# ESP32_Sheet.net
KiCad netlist of a schematic drawn in Altium Designer
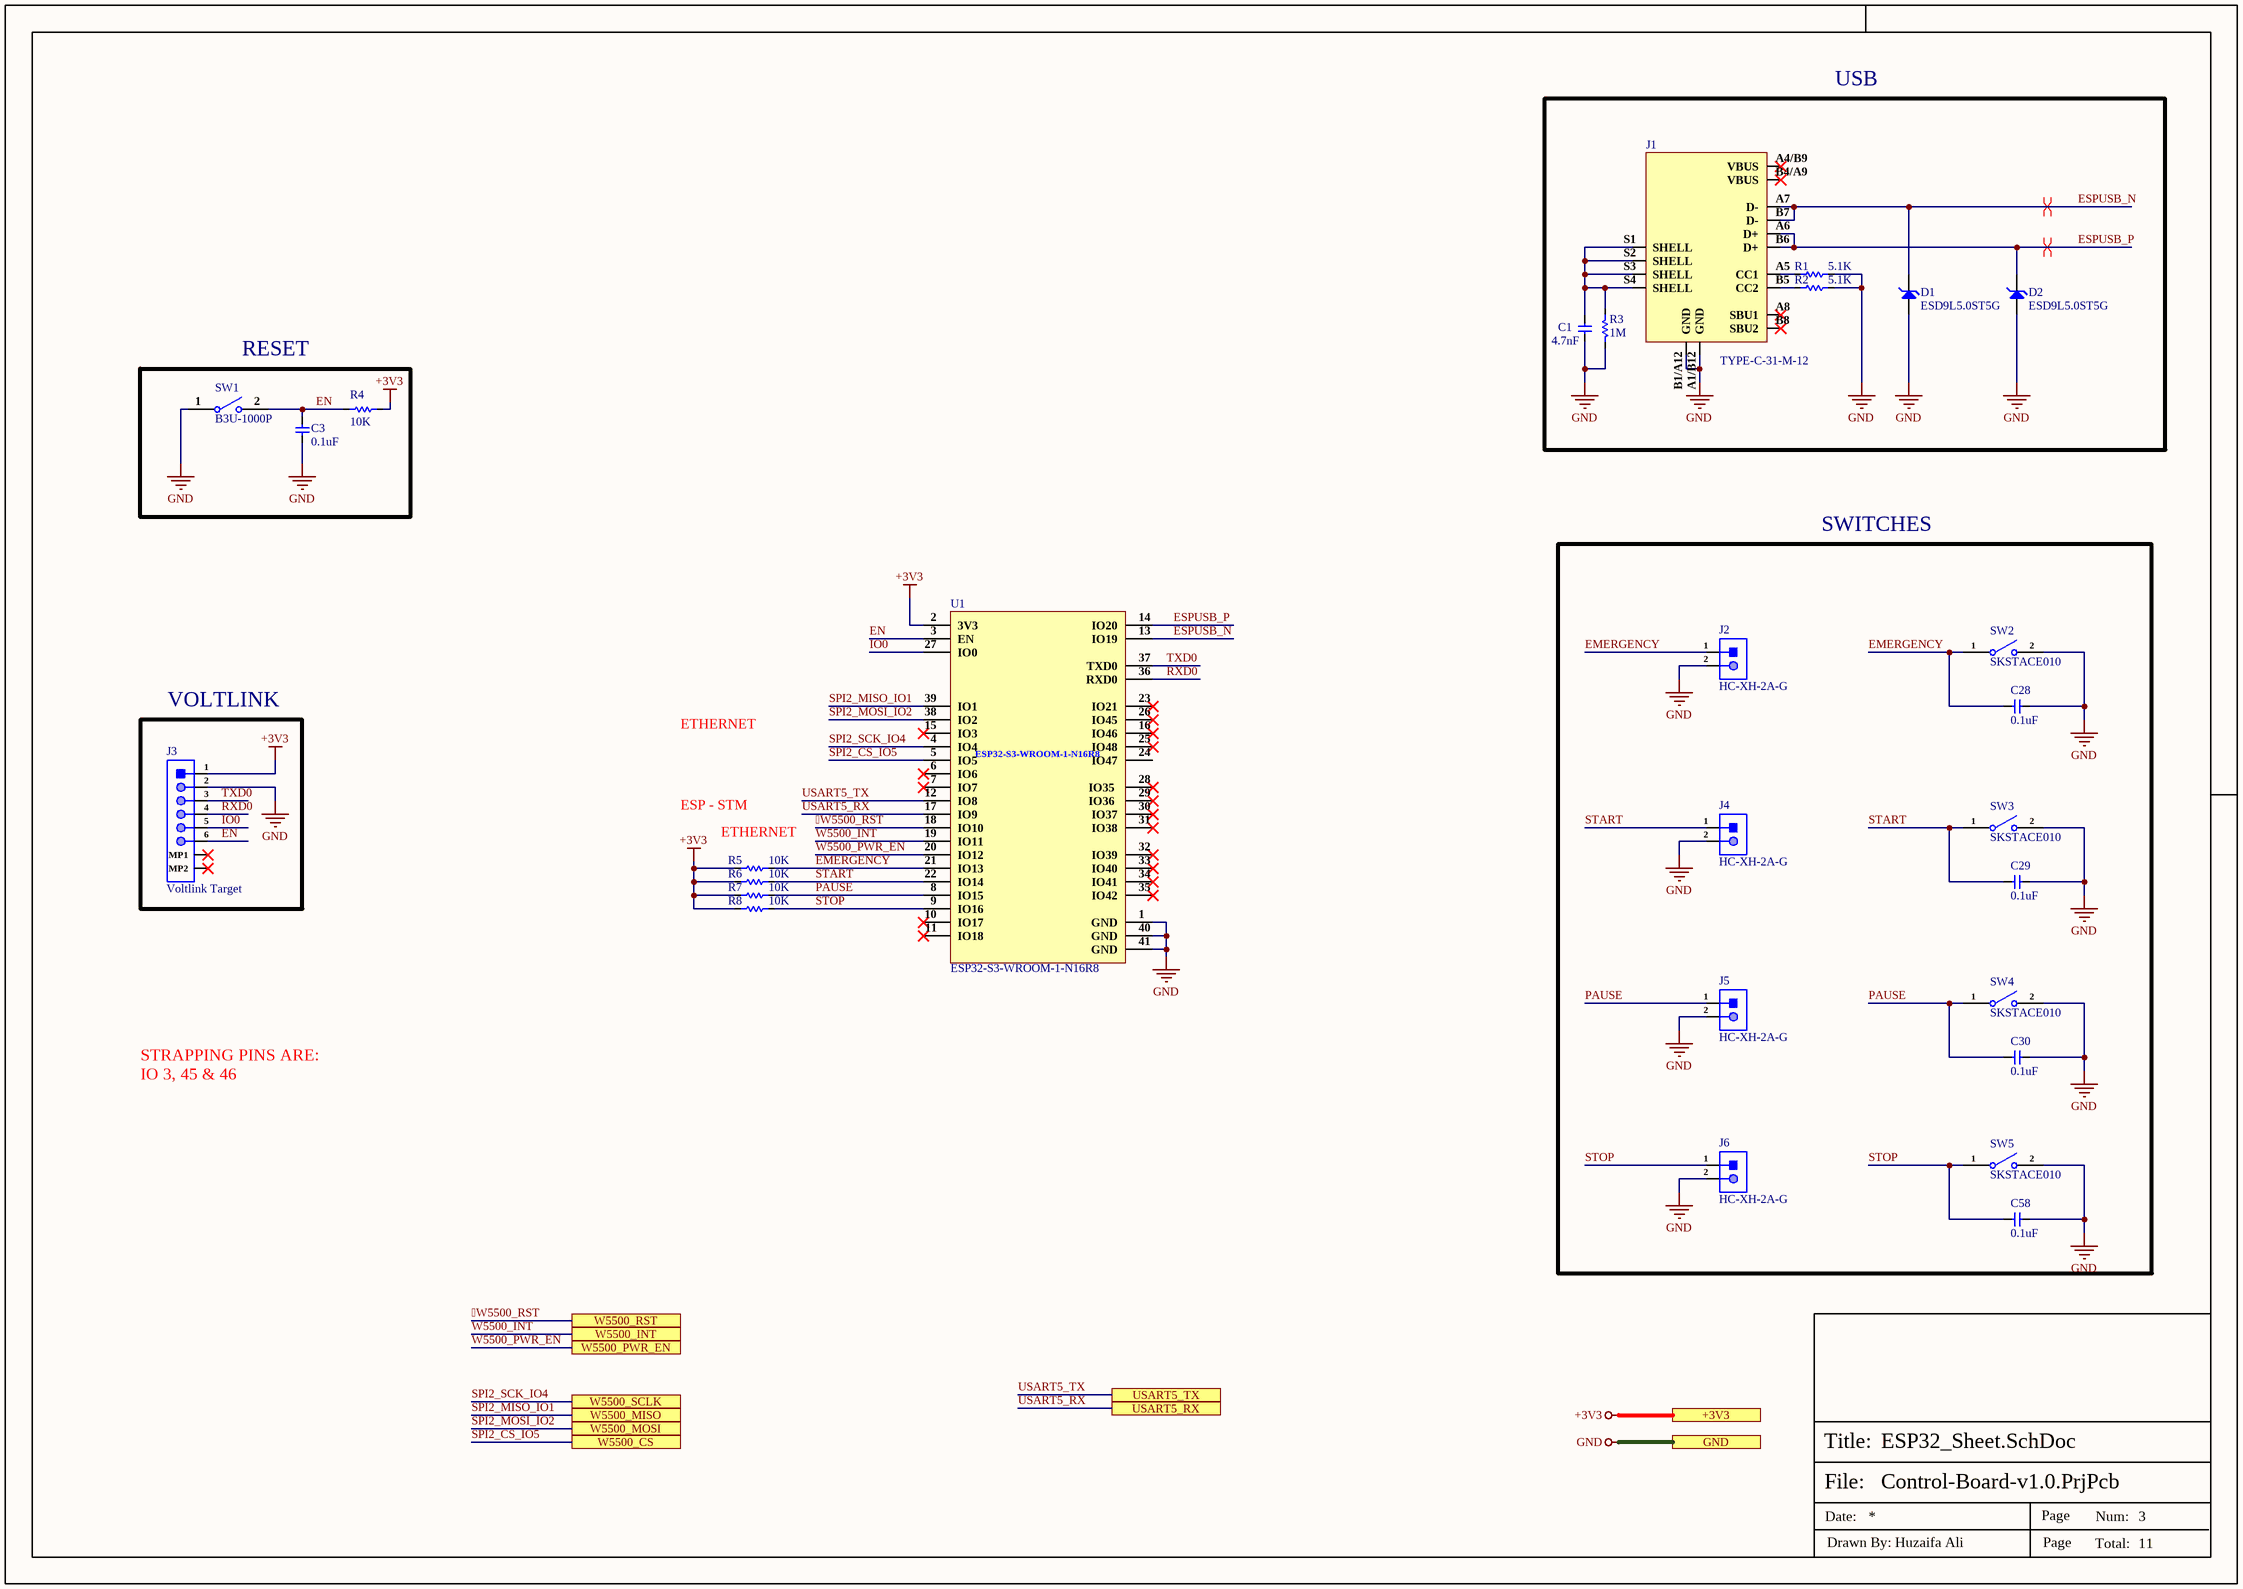
[diagram p0: ESP32_Sheet.SchDoc]

(export (version "E")
  (design (tool "Eeschema 10.0.6"))
  (components
    (comp (ref "C1")
      (value "4.7nF")
      (footprint "Cap-0603")
      (description "CAP CER 4700PF 50V C0G/NPO 0603")
      (fields
        (field (name "MANUFACTURER") "Yageo")
        (field (name "MANUFACTURER PART NUMBER") "CC0603JRNPO9BN472")
      )
      (libsource (lib "eSpark_centralized_Library(2022)") (part "CC0603JRNPO9BN472"))
    )
    (comp (ref "C3")
      (value "0.1uF")
      (footprint "Cap-0402")
      (description "CAP CER 0.1UF 16V X7R 0402")
      (fields
        (field (name "MANUFACTURER") "Yageo")
        (field (name "MANUFACTURER PART NUMBER") "CC0402JRX7R7BB104")
      )
      (libsource (lib "eSpark Libraries") (part "CC0402JRX7R7BB104"))
    )
    (comp (ref "C28")
      (value "0.1uF")
      (footprint "Cap-0402")
      (description "CAP CER 0.1UF 16V X7R 0402")
      (fields
        (field (name "MANUFACTURER") "Yageo")
        (field (name "MANUFACTURER PART NUMBER") "CC0402JRX7R7BB104")
      )
      (libsource (lib "eSpark Libraries") (part "CC0402JRX7R7BB104"))
    )
    (comp (ref "C29")
      (value "0.1uF")
      (footprint "Cap-0402")
      (description "CAP CER 0.1UF 16V X7R 0402")
      (fields
        (field (name "MANUFACTURER") "Yageo")
        (field (name "MANUFACTURER PART NUMBER") "CC0402JRX7R7BB104")
      )
      (libsource (lib "eSpark Libraries") (part "CC0402JRX7R7BB104"))
    )
    (comp (ref "C30")
      (value "0.1uF")
      (footprint "Cap-0402")
      (description "CAP CER 0.1UF 16V X7R 0402")
      (fields
        (field (name "MANUFACTURER") "Yageo")
        (field (name "MANUFACTURER PART NUMBER") "CC0402JRX7R7BB104")
      )
      (libsource (lib "eSpark Libraries") (part "CC0402JRX7R7BB104"))
    )
    (comp (ref "C58")
      (value "0.1uF")
      (footprint "Cap-0402")
      (description "CAP CER 0.1UF 16V X7R 0402")
      (fields
        (field (name "MANUFACTURER") "Yageo")
        (field (name "MANUFACTURER PART NUMBER") "CC0402JRX7R7BB104")
      )
      (libsource (lib "eSpark Libraries") (part "CC0402JRX7R7BB104"))
    )
    (comp (ref "D1")
      (value "ESD9L5.0ST5G")
      (footprint "SOD-923.")
      (description "TVS DIODE 5V 9.8V SOD923")
      (fields (field (name "MANUFACTURER") "ON Semiconductor") (field (name "LCSC PART NUMBER") "C82326"))
      (libsource (lib "eSpark Libraries") (part "ESD9L5.0ST5G"))
    )
    (comp (ref "D2")
      (value "ESD9L5.0ST5G")
      (footprint "SOD-923.")
      (description "TVS DIODE 5V 9.8V SOD923")
      (fields (field (name "MANUFACTURER") "ON Semiconductor") (field (name "LCSC PART NUMBER") "C82326"))
      (libsource (lib "eSpark Libraries") (part "ESD9L5.0ST5G"))
    )
    (comp (ref "J1")
      (value "TYPE-C-31-M-12")
      (footprint "TYPE-C-31-M-12_")
      (description "5A 1 16P Female Type-C SMD USB Connectors ROHS")
      (fields
        (field (name "MANUFACTURER") "Korean Hroparts Elec")
        (field (name "LCSC PART NUMBER") "C165948")
      )
      (libsource (lib "eSpark Libraries") (part "TYPE-C-31-M-12"))
    )
    (comp (ref "J2")
      (value "HC-XH-2A-G")
      (footprint "HC-XH-2A-G")
      (fields (field (name "MANUFACTURER") "HCTL") (field (name "LCSC PART NUMBER") "C5341201"))
      (libsource (lib "eSpark Libraries") (part "HC-XH-2A-G"))
    )
    (comp (ref "J3")
      (value "Voltlink Target")
      (footprint "Voltlink Target")
      (description "1x6P SH 1 1mm 6 SMD,P=1mm Wire To Board / Wire To Wire Connector ROHS")
      (fields (field (name "MANUFACTURER") "BOOMELE") (field (name "MANUFACTURER PART NUMBER") "C145963"))
      (libsource (lib "eSpark Libraries") (part "C145963"))
    )
    (comp (ref "J4")
      (value "HC-XH-2A-G")
      (footprint "HC-XH-2A-G")
      (fields (field (name "MANUFACTURER") "HCTL") (field (name "LCSC PART NUMBER") "C5341201"))
      (libsource (lib "eSpark Libraries") (part "HC-XH-2A-G"))
    )
    (comp (ref "J5")
      (value "HC-XH-2A-G")
      (footprint "HC-XH-2A-G")
      (fields (field (name "MANUFACTURER") "HCTL") (field (name "LCSC PART NUMBER") "C5341201"))
      (libsource (lib "eSpark Libraries") (part "HC-XH-2A-G"))
    )
    (comp (ref "J6")
      (value "HC-XH-2A-G")
      (footprint "HC-XH-2A-G")
      (fields (field (name "MANUFACTURER") "HCTL") (field (name "LCSC PART NUMBER") "C5341201"))
      (libsource (lib "eSpark Libraries") (part "HC-XH-2A-G"))
    )
    (comp (ref "R1")
      (value "5.1K")
      (footprint "Res-0402")
      (description "RES 5.1K OHM 1% 1/16W 0402")
      (fields
        (field (name "MANUFACTURER") "Yageo")
        (field (name "MANUFACTURER PART NUMBER") "RC0402FR-075K1L")
      )
      (libsource (lib "eSpark Libraries") (part "RC0402FR-075K1L"))
    )
    (comp (ref "R2")
      (value "5.1K")
      (footprint "Res-0402")
      (description "RES 5.1K OHM 1% 1/16W 0402")
      (fields
        (field (name "MANUFACTURER") "Yageo")
        (field (name "MANUFACTURER PART NUMBER") "RC0402FR-075K1L")
      )
      (libsource (lib "eSpark Libraries") (part "RC0402FR-075K1L"))
    )
    (comp (ref "R3")
      (value "1M")
      (footprint "Res-0402")
      (description "RES SMD 1M OHM 5% 1/16W 0402")
      (fields
        (field (name "MANUFACTURER") "Yageo")
        (field (name "MANUFACTURER PART NUMBER") "AF0402JR-071ML")
      )
      (libsource (lib "eSpark_centralized_Library(2022)") (part "AF0402JR-071ML"))
    )
    (comp (ref "R4")
      (value "10K")
      (footprint "Res-0402")
      (description "RES 10K OHM 1% 1/16W 0402")
      (fields
        (field (name "MANUFACTURER") "Yageo")
        (field (name "MANUFACTURER PART NUMBER") "RC0402FR-0710KL")
      )
      (libsource (lib "eSpark Libraries") (part "RC0402FR-0710KL"))
    )
    (comp (ref "R5")
      (value "10K")
      (footprint "Res-0402")
      (description "RES 10K OHM 1% 1/16W 0402")
      (fields
        (field (name "MANUFACTURER") "Yageo")
        (field (name "MANUFACTURER PART NUMBER") "RC0402FR-0710KL")
      )
      (libsource (lib "eSpark Libraries") (part "RC0402FR-0710KL"))
    )
    (comp (ref "R6")
      (value "10K")
      (footprint "Res-0402")
      (description "RES 10K OHM 1% 1/16W 0402")
      (fields
        (field (name "MANUFACTURER") "Yageo")
        (field (name "MANUFACTURER PART NUMBER") "RC0402FR-0710KL")
      )
      (libsource (lib "eSpark Libraries") (part "RC0402FR-0710KL"))
    )
    (comp (ref "R7")
      (value "10K")
      (footprint "Res-0402")
      (description "RES 10K OHM 1% 1/16W 0402")
      (fields
        (field (name "MANUFACTURER") "Yageo")
        (field (name "MANUFACTURER PART NUMBER") "RC0402FR-0710KL")
      )
      (libsource (lib "eSpark Libraries") (part "RC0402FR-0710KL"))
    )
    (comp (ref "R8")
      (value "10K")
      (footprint "Res-0402")
      (description "RES 10K OHM 1% 1/16W 0402")
      (fields
        (field (name "MANUFACTURER") "Yageo")
        (field (name "MANUFACTURER PART NUMBER") "RC0402FR-0710KL")
      )
      (libsource (lib "eSpark Libraries") (part "RC0402FR-0710KL"))
    )
    (comp (ref "SW1")
      (value "B3U-1000P")
      (footprint "B3U-1000P")
      (description "SWITCH TACTILE SPST-NO 0.05A 12V")
      (fields (field (name "MANUFACTURER") "Omron") (field (name "LCSC PART NUMBER") "C231329"))
      (libsource (lib "eSpark Libraries") (part "B3U-1000P"))
    )
    (comp (ref "SW2")
      (value "SKSTACE010")
      (footprint "SKSTACE010_")
      (description "Tactile Switches SMT Top Push 0.9mm 7N Trav 100m Yellow")
      (fields (field (name "MANUFACTURER") "Alps Electric") (field (name "LCSC PART NUMBER") "C341731"))
      (libsource (lib "eSpark Libraries") (part "SKSTACE010"))
    )
    (comp (ref "SW3")
      (value "SKSTACE010")
      (footprint "SKSTACE010_")
      (description "Tactile Switches SMT Top Push 0.9mm 7N Trav 100m Yellow")
      (fields (field (name "MANUFACTURER") "Alps Electric") (field (name "LCSC PART NUMBER") "C341731"))
      (libsource (lib "eSpark Libraries") (part "SKSTACE010"))
    )
    (comp (ref "SW4")
      (value "SKSTACE010")
      (footprint "SKSTACE010_")
      (description "Tactile Switches SMT Top Push 0.9mm 7N Trav 100m Yellow")
      (fields (field (name "MANUFACTURER") "Alps Electric") (field (name "LCSC PART NUMBER") "C341731"))
      (libsource (lib "eSpark Libraries") (part "SKSTACE010"))
    )
    (comp (ref "SW5")
      (value "SKSTACE010")
      (footprint "SKSTACE010_")
      (description "Tactile Switches SMT Top Push 0.9mm 7N Trav 100m Yellow")
      (fields (field (name "MANUFACTURER") "Alps Electric") (field (name "LCSC PART NUMBER") "C341731"))
      (libsource (lib "eSpark Libraries") (part "SKSTACE010"))
    )
    (comp (ref "U1")
      (value "ESP32-S3-WROOM-1-N16R8")
      (footprint "41-SMD Module")
      (description "SMD MODULE, ESP32-S3R8 WITH 3.3V")
      (fields (field (name "MANUFACTURER") "Espressif Systems") (field (name "LCSC PART NUMBER") "C2913202"))
      (libsource (lib "eSpark Libraries") (part "ESP32-S3-WROOM-1-N16R8"))
    )
  )
  (nets
    (net (code "1") (name "+3V3") (class "Default")
      (node (ref "J3") (pin "1") (pinfunction "1_1") (pintype "passive"))
      (node (ref "R4") (pin "2") (pinfunction "2_2") (pintype "passive"))
      (node (ref "R5") (pin "1") (pinfunction "1_1") (pintype "passive"))
      (node (ref "R6") (pin "1") (pinfunction "1_1") (pintype "passive"))
      (node (ref "R7") (pin "1") (pinfunction "1_1") (pintype "passive"))
      (node (ref "R8") (pin "1") (pinfunction "1_1") (pintype "passive"))
      (node (ref "U1") (pin "2") (pinfunction "3V3_2") (pintype "passive"))
    )
    (net (code "2") (name "/W5500_RST") (class "Default")
      (node (ref "U1") (pin "18") (pinfunction "IO10_18") (pintype "passive"))
    )
    (net (code "3") (name "/EMERGENCY") (class "Default")
      (node (ref "C28") (pin "2") (pinfunction "2_2") (pintype "passive"))
      (node (ref "J2") (pin "1") (pinfunction "1_1") (pintype "passive"))
      (node (ref "R5") (pin "2") (pinfunction "2_2") (pintype "passive"))
      (node (ref "SW2") (pin "1") (pinfunction "1_1") (pintype "passive"))
      (node (ref "U1") (pin "21") (pinfunction "IO13_21") (pintype "passive"))
    )
    (net (code "4") (name "/EN") (class "Default")
      (node (ref "C3") (pin "2") (pinfunction "2_2") (pintype "passive"))
      (node (ref "J3") (pin "6") (pinfunction "6_6") (pintype "passive"))
      (node (ref "R4") (pin "1") (pinfunction "1_1") (pintype "passive"))
      (node (ref "SW1") (pin "2") (pinfunction "2_2") (pintype "passive"))
      (node (ref "U1") (pin "3") (pinfunction "EN_3") (pintype "passive"))
    )
    (net (code "5") (name "/ESPUSB_N") (class "Default")
      (node (ref "D1") (pin "1") (pinfunction "K_1") (pintype "passive"))
      (node (ref "J1") (pin "A7") (pinfunction "D-_A7") (pintype "passive"))
      (node (ref "J1") (pin "B7") (pinfunction "D-_B7") (pintype "passive"))
      (node (ref "U1") (pin "13") (pinfunction "IO19_13") (pintype "passive"))
    )
    (net (code "6") (name "/ESPUSB_P") (class "Default")
      (node (ref "D2") (pin "1") (pinfunction "K_1") (pintype "passive"))
      (node (ref "J1") (pin "A6") (pinfunction "D+_A6") (pintype "passive"))
      (node (ref "J1") (pin "B6") (pinfunction "D+_B6") (pintype "passive"))
      (node (ref "U1") (pin "14") (pinfunction "IO20_14") (pintype "passive"))
    )
    (net (code "7") (name "/IO0") (class "Default")
      (node (ref "J3") (pin "5") (pinfunction "5_5") (pintype "passive"))
      (node (ref "U1") (pin "27") (pinfunction "IO0_27") (pintype "passive"))
    )
    (net (code "8") (name "/PAUSE") (class "Default")
      (node (ref "C30") (pin "2") (pinfunction "2_2") (pintype "passive"))
      (node (ref "J5") (pin "1") (pinfunction "1_1") (pintype "passive"))
      (node (ref "R7") (pin "2") (pinfunction "2_2") (pintype "passive"))
      (node (ref "SW4") (pin "1") (pinfunction "1_1") (pintype "passive"))
      (node (ref "U1") (pin "8") (pinfunction "IO15_8") (pintype "passive"))
    )
    (net (code "9") (name "/RXD0") (class "Default")
      (node (ref "J3") (pin "4") (pinfunction "4_4") (pintype "passive"))
      (node (ref "U1") (pin "36") (pinfunction "RXD0_36") (pintype "passive"))
    )
    (net (code "10") (name "/SPI2_CS_IO5") (class "Default")
      (node (ref "U1") (pin "5") (pinfunction "IO5_5") (pintype "passive"))
    )
    (net (code "11") (name "/SPI2_MISO_IO1") (class "Default")
      (node (ref "U1") (pin "39") (pinfunction "IO1_39") (pintype "passive"))
    )
    (net (code "12") (name "/SPI2_MOSI_IO2") (class "Default")
      (node (ref "U1") (pin "38") (pinfunction "IO2_38") (pintype "passive"))
    )
    (net (code "13") (name "/SPI2_SCK_IO4") (class "Default")
      (node (ref "U1") (pin "4") (pinfunction "IO4_4") (pintype "passive"))
    )
    (net (code "14") (name "/START") (class "Default")
      (node (ref "C29") (pin "2") (pinfunction "2_2") (pintype "passive"))
      (node (ref "J4") (pin "1") (pinfunction "1_1") (pintype "passive"))
      (node (ref "R6") (pin "2") (pinfunction "2_2") (pintype "passive"))
      (node (ref "SW3") (pin "1") (pinfunction "1_1") (pintype "passive"))
      (node (ref "U1") (pin "22") (pinfunction "IO14_22") (pintype "passive"))
    )
    (net (code "15") (name "/STOP") (class "Default")
      (node (ref "C58") (pin "2") (pinfunction "2_2") (pintype "passive"))
      (node (ref "J6") (pin "1") (pinfunction "1_1") (pintype "passive"))
      (node (ref "R8") (pin "2") (pinfunction "2_2") (pintype "passive"))
      (node (ref "SW5") (pin "1") (pinfunction "1_1") (pintype "passive"))
      (node (ref "U1") (pin "9") (pinfunction "IO16_9") (pintype "passive"))
    )
    (net (code "16") (name "/TXD0") (class "Default")
      (node (ref "J3") (pin "3") (pinfunction "3_3") (pintype "passive"))
      (node (ref "U1") (pin "37") (pinfunction "TXD0_37") (pintype "passive"))
    )
    (net (code "17") (name "/USART5_RX") (class "Default")
      (node (ref "U1") (pin "17") (pinfunction "IO9_17") (pintype "passive"))
    )
    (net (code "18") (name "/USART5_TX") (class "Default")
      (node (ref "U1") (pin "12") (pinfunction "IO8_12") (pintype "passive"))
    )
    (net (code "19") (name "/W5500_INT") (class "Default")
      (node (ref "U1") (pin "19") (pinfunction "IO11_19") (pintype "passive"))
    )
    (net (code "20") (name "/W5500_PWR_EN") (class "Default")
      (node (ref "U1") (pin "20") (pinfunction "IO12_20") (pintype "passive"))
    )
    (net (code "21") (name "GND") (class "Default")
      (node (ref "C1") (pin "1") (pinfunction "1_1") (pintype "passive"))
      (node (ref "C28") (pin "1") (pinfunction "1_1") (pintype "passive"))
      (node (ref "C29") (pin "1") (pinfunction "1_1") (pintype "passive"))
      (node (ref "C3") (pin "1") (pinfunction "1_1") (pintype "passive"))
      (node (ref "C30") (pin "1") (pinfunction "1_1") (pintype "passive"))
      (node (ref "C58") (pin "1") (pinfunction "1_1") (pintype "passive"))
      (node (ref "D1") (pin "2") (pinfunction "A_2") (pintype "passive"))
      (node (ref "D2") (pin "2") (pinfunction "A_2") (pintype "passive"))
      (node (ref "J1") (pin "A1/B12") (pinfunction "GND_A1/B12") (pintype "power_in"))
      (node (ref "J1") (pin "B1/A12") (pinfunction "GND_B1/A12") (pintype "power_in"))
      (node (ref "J2") (pin "2") (pinfunction "2_2") (pintype "passive"))
      (node (ref "J3") (pin "2") (pinfunction "2_2") (pintype "passive"))
      (node (ref "J4") (pin "2") (pinfunction "2_2") (pintype "passive"))
      (node (ref "J5") (pin "2") (pinfunction "2_2") (pintype "passive"))
      (node (ref "J6") (pin "2") (pinfunction "2_2") (pintype "passive"))
      (node (ref "R1") (pin "2") (pinfunction "2_2") (pintype "passive"))
      (node (ref "R2") (pin "2") (pinfunction "2_2") (pintype "passive"))
      (node (ref "R3") (pin "2") (pinfunction "2_2") (pintype "passive"))
      (node (ref "SW1") (pin "1") (pinfunction "1_1") (pintype "passive"))
      (node (ref "SW2") (pin "2") (pinfunction "2_2") (pintype "passive"))
      (node (ref "SW3") (pin "2") (pinfunction "2_2") (pintype "passive"))
      (node (ref "SW4") (pin "2") (pinfunction "2_2") (pintype "passive"))
      (node (ref "SW5") (pin "2") (pinfunction "2_2") (pintype "passive"))
      (node (ref "U1") (pin "1") (pinfunction "GND_1") (pintype "passive"))
      (node (ref "U1") (pin "40") (pinfunction "GND_40") (pintype "passive"))
      (node (ref "U1") (pin "41") (pinfunction "GND_41") (pintype "passive"))
    )
    (net (code "22") (name "Net-(C1-Pad2)") (class "Default")
      (node (ref "C1") (pin "2") (pinfunction "2_2") (pintype "passive"))
      (node (ref "J1") (pin "S1") (pinfunction "SHELL_S1") (pintype "passive"))
      (node (ref "J1") (pin "S2") (pinfunction "SHELL_S2") (pintype "passive"))
      (node (ref "J1") (pin "S3") (pinfunction "SHELL_S3") (pintype "passive"))
      (node (ref "J1") (pin "S4") (pinfunction "SHELL_S4") (pintype "passive"))
      (node (ref "R3") (pin "1") (pinfunction "1_1") (pintype "passive"))
    )
    (net (code "23") (name "Net-(J1-CC1)") (class "Default")
      (node (ref "J1") (pin "A5") (pinfunction "CC1_A5") (pintype "passive"))
      (node (ref "R1") (pin "1") (pinfunction "1_1") (pintype "passive"))
    )
    (net (code "24") (name "Net-(J1-CC2)") (class "Default")
      (node (ref "J1") (pin "B5") (pinfunction "CC2_B5") (pintype "passive"))
      (node (ref "R2") (pin "1") (pinfunction "1_1") (pintype "passive"))
    )
    (net (code "25") (name "unconnected-(J1-SBU1-PadA8)") (class "Default")
      (node (ref "J1") (pin "A8") (pinfunction "SBU1_A8") (pintype "passive+no_connect"))
    )
    (net (code "26") (name "unconnected-(J1-SBU2-PadB8)") (class "Default")
      (node (ref "J1") (pin "B8") (pinfunction "SBU2_B8") (pintype "passive+no_connect"))
    )
    (net (code "27") (name "unconnected-(J1-VBUS-PadA4{slash}B9)") (class "Default")
      (node (ref "J1") (pin "A4/B9") (pinfunction "VBUS_A4/B9") (pintype "power_in+no_connect"))
    )
    (net (code "28") (name "unconnected-(J1-VBUS-PadB4{slash}A9)") (class "Default")
      (node (ref "J1") (pin "B4/A9") (pinfunction "VBUS_B4/A9") (pintype "power_in+no_connect"))
    )
    (net (code "29") (name "unconnected-(J3-PadMP1)") (class "Default")
      (node (ref "J3") (pin "MP1") (pinfunction "MP1_MP1") (pintype "passive+no_connect"))
    )
    (net (code "30") (name "unconnected-(J3-PadMP2)") (class "Default")
      (node (ref "J3") (pin "MP2") (pinfunction "MP2_MP2") (pintype "passive+no_connect"))
    )
    (net (code "31") (name "unconnected-(U1-IO3-Pad15)") (class "Default")
      (node (ref "U1") (pin "15") (pinfunction "IO3_15") (pintype "passive+no_connect"))
    )
    (net (code "32") (name "unconnected-(U1-IO6-Pad6)") (class "Default")
      (node (ref "U1") (pin "6") (pinfunction "IO6_6") (pintype "passive+no_connect"))
    )
    (net (code "33") (name "unconnected-(U1-IO7-Pad7)") (class "Default")
      (node (ref "U1") (pin "7") (pinfunction "IO7_7") (pintype "passive+no_connect"))
    )
    (net (code "34") (name "unconnected-(U1-IO17-Pad10)") (class "Default")
      (node (ref "U1") (pin "10") (pinfunction "IO17_10") (pintype "passive+no_connect"))
    )
    (net (code "35") (name "unconnected-(U1-IO18-Pad11)") (class "Default")
      (node (ref "U1") (pin "11") (pinfunction "IO18_11") (pintype "passive+no_connect"))
    )
    (net (code "36") (name "unconnected-(U1-IO21-Pad23)") (class "Default")
      (node (ref "U1") (pin "23") (pinfunction "IO21_23") (pintype "passive+no_connect"))
    )
    (net (code "37") (name "unconnected-(U1-IO35-Pad28)") (class "Default")
      (node (ref "U1") (pin "28") (pinfunction "IO35_28") (pintype "passive+no_connect"))
    )
    (net (code "38") (name "unconnected-(U1-IO36-Pad29)") (class "Default")
      (node (ref "U1") (pin "29") (pinfunction "IO36_29") (pintype "passive+no_connect"))
    )
    (net (code "39") (name "unconnected-(U1-IO37-Pad30)") (class "Default")
      (node (ref "U1") (pin "30") (pinfunction "IO37_30") (pintype "passive+no_connect"))
    )
    (net (code "40") (name "unconnected-(U1-IO38-Pad31)") (class "Default")
      (node (ref "U1") (pin "31") (pinfunction "IO38_31") (pintype "passive+no_connect"))
    )
    (net (code "41") (name "unconnected-(U1-IO39-Pad32)") (class "Default")
      (node (ref "U1") (pin "32") (pinfunction "IO39_32") (pintype "passive+no_connect"))
    )
    (net (code "42") (name "unconnected-(U1-IO40-Pad33)") (class "Default")
      (node (ref "U1") (pin "33") (pinfunction "IO40_33") (pintype "passive+no_connect"))
    )
    (net (code "43") (name "unconnected-(U1-IO41-Pad34)") (class "Default")
      (node (ref "U1") (pin "34") (pinfunction "IO41_34") (pintype "passive+no_connect"))
    )
    (net (code "44") (name "unconnected-(U1-IO42-Pad35)") (class "Default")
      (node (ref "U1") (pin "35") (pinfunction "IO42_35") (pintype "passive+no_connect"))
    )
    (net (code "45") (name "unconnected-(U1-IO45-Pad26)") (class "Default")
      (node (ref "U1") (pin "26") (pinfunction "IO45_26") (pintype "passive+no_connect"))
    )
    (net (code "46") (name "unconnected-(U1-IO46-Pad16)") (class "Default")
      (node (ref "U1") (pin "16") (pinfunction "IO46_16") (pintype "passive+no_connect"))
    )
    (net (code "47") (name "unconnected-(U1-IO47-Pad24)") (class "Default")
      (node (ref "U1") (pin "24") (pinfunction "IO47_24") (pintype "passive"))
    )
    (net (code "48") (name "unconnected-(U1-IO48-Pad25)") (class "Default")
      (node (ref "U1") (pin "25") (pinfunction "IO48_25") (pintype "passive+no_connect"))
    )
  )
)
